# V2.net
KiCad netlist of a schematic drawn in EAGLE
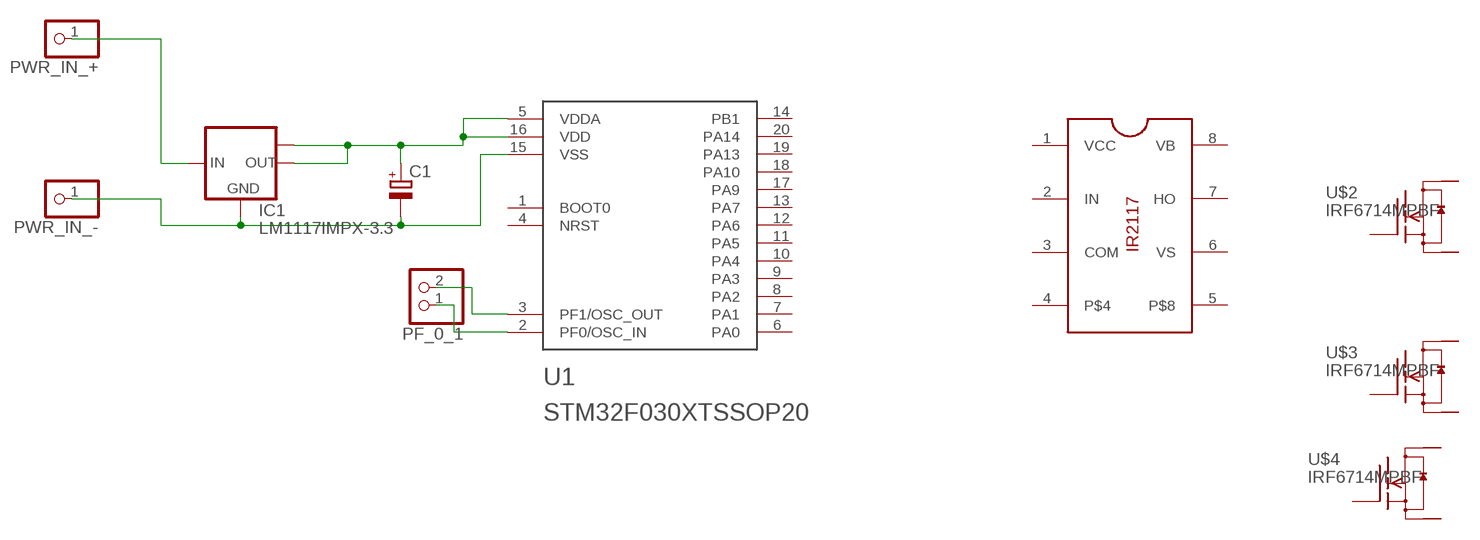
[diagram p0: schematic, sheet 1]

(export (version "E")
  (design (tool "Eeschema 10.0.6"))
  (components
    (comp (ref "C1")
      (value "CPOL-EUSMCD")
      (footprint "eagle-import:SMC_D")
      (libsource (lib "eagle-import") (part "CPOL-EUSMCD"))
    )
    (comp (ref "IC1")
      (value "LM1117IMPX-3.3")
      (footprint "eagle-import:SOT223")
      (libsource (lib "eagle-import") (part "LM1117IMPX-3.3"))
    )
    (comp (ref "PF_0_1")
      (value "PINHD-1X2")
      (footprint "eagle-import:1X02")
      (libsource (lib "eagle-import") (part "PINHD-1X2"))
    )
    (comp (ref "PWR_IN_+")
      (value "PINHD-1X1")
      (footprint "eagle-import:1X01")
      (libsource (lib "eagle-import") (part "PINHD-1X1"))
    )
    (comp (ref "PWR_IN_-")
      (value "PINHD-1X1")
      (footprint "eagle-import:1X01")
      (libsource (lib "eagle-import") (part "PINHD-1X1"))
    )
    (comp (ref "U$1")
      (value "IR2117SPBF")
      (footprint "eagle-import:SO8")
      (libsource (lib "eagle-import") (part "IR2117SPBF"))
    )
    (comp (ref "U$2")
      (value "IRF6714MPBF")
      (footprint "eagle-import:DIRECTFET-MX")
      (libsource (lib "eagle-import") (part "IRF6714MPBF"))
    )
    (comp (ref "U$3")
      (value "IRF6714MPBF")
      (footprint "eagle-import:DIRECTFET-MX")
      (libsource (lib "eagle-import") (part "IRF6714MPBF"))
    )
    (comp (ref "U$4")
      (value "IRF6714MPBF")
      (footprint "eagle-import:DIRECTFET-MX")
      (libsource (lib "eagle-import") (part "IRF6714MPBF"))
    )
    (comp (ref "U1")
      (value "STM32F030XTSSOP20")
      (footprint "eagle-import:TSSOP-20")
      (libsource (lib "eagle-import") (part "STM32F030XTSSOP20"))
    )
  )
  (nets
    (net (code "1") (name "Net-(IC1-GND)") (class "Default")
      (node (ref "C1") (pin "-") (pinfunction "-_-") (pintype "passive"))
      (node (ref "IC1") (pin "1") (pinfunction "GND_1") (pintype "input"))
      (node (ref "PWR_IN_-") (pin "1") (pinfunction "1_1") (pintype "passive"))
      (node (ref "U1") (pin "15") (pinfunction "VSS_15") (pintype "bidirectional"))
    )
    (net (code "2") (name "Net-(IC1-IN)") (class "Default")
      (node (ref "IC1") (pin "3") (pinfunction "IN_3") (pintype "input"))
      (node (ref "PWR_IN_+") (pin "1") (pinfunction "1_1") (pintype "passive"))
    )
    (net (code "3") (name "Net-(IC1-OUT)") (class "Default")
      (node (ref "C1") (pin "+") (pinfunction "+_+") (pintype "passive"))
      (node (ref "IC1") (pin "2") (pinfunction "OUT_2") (pintype "passive"))
      (node (ref "IC1") (pin "TAB") (pinfunction "OUT1_TAB") (pintype "passive"))
      (node (ref "U1") (pin "16") (pinfunction "VDD_16") (pintype "bidirectional"))
      (node (ref "U1") (pin "5") (pinfunction "VDDA_5") (pintype "bidirectional"))
    )
    (net (code "4") (name "Net-(U1-PF0{slash}OSC_IN)") (class "Default")
      (node (ref "PF_0_1") (pin "1") (pinfunction "1_1") (pintype "passive"))
      (node (ref "U1") (pin "2") (pinfunction "PF0/OSC_IN_2") (pintype "bidirectional"))
    )
    (net (code "5") (name "Net-(U1-PF1{slash}OSC_OUT)") (class "Default")
      (node (ref "PF_0_1") (pin "2") (pinfunction "2_2") (pintype "passive"))
      (node (ref "U1") (pin "3") (pinfunction "PF1/OSC_OUT_3") (pintype "bidirectional"))
    )
    (net (code "6") (name "unconnected-(U$1-COM-Pad3)") (class "Default")
      (node (ref "U$1") (pin "3") (pinfunction "COM_3") (pintype "bidirectional"))
    )
    (net (code "7") (name "unconnected-(U$1-HO-Pad7)") (class "Default")
      (node (ref "U$1") (pin "7") (pinfunction "HO_7") (pintype "bidirectional"))
    )
    (net (code "8") (name "unconnected-(U$1-IN-Pad2)") (class "Default")
      (node (ref "U$1") (pin "2") (pinfunction "IN_2") (pintype "bidirectional"))
    )
    (net (code "9") (name "unconnected-(U$1-P$4-Pad4)") (class "Default")
      (node (ref "U$1") (pin "4") (pinfunction "P$4_4") (pintype "bidirectional"))
    )
    (net (code "10") (name "unconnected-(U$1-P$8-Pad5)") (class "Default")
      (node (ref "U$1") (pin "5") (pinfunction "P$8_5") (pintype "bidirectional"))
    )
    (net (code "11") (name "unconnected-(U$1-VB-Pad8)") (class "Default")
      (node (ref "U$1") (pin "8") (pinfunction "VB_8") (pintype "bidirectional"))
    )
    (net (code "12") (name "unconnected-(U$1-VCC-Pad1)") (class "Default")
      (node (ref "U$1") (pin "1") (pinfunction "VCC_1") (pintype "bidirectional"))
    )
    (net (code "13") (name "unconnected-(U$1-VS-Pad6)") (class "Default")
      (node (ref "U$1") (pin "6") (pinfunction "VS_6") (pintype "bidirectional"))
    )
    (net (code "14") (name "unconnected-(U$2-D-PadD(V))") (class "Default")
      (node (ref "U$2") (pin "D(V)") (pinfunction "D_D(V)") (pintype "passive"))
    )
    (net (code "15") (name "unconnected-(U$2-PadG)") (class "Default")
      (node (ref "U$2") (pin "G") (pinfunction "G_G") (pintype "passive"))
    )
    (net (code "16") (name "unconnected-(U$2-PadS)") (class "Default")
      (node (ref "U$2") (pin "S") (pinfunction "S_S") (pintype "passive"))
    )
    (net (code "17") (name "unconnected-(U$3-D-PadD(V))") (class "Default")
      (node (ref "U$3") (pin "D(V)") (pinfunction "D_D(V)") (pintype "passive"))
    )
    (net (code "18") (name "unconnected-(U$3-PadG)") (class "Default")
      (node (ref "U$3") (pin "G") (pinfunction "G_G") (pintype "passive"))
    )
    (net (code "19") (name "unconnected-(U$3-PadS)") (class "Default")
      (node (ref "U$3") (pin "S") (pinfunction "S_S") (pintype "passive"))
    )
    (net (code "20") (name "unconnected-(U$4-D-PadD(V))") (class "Default")
      (node (ref "U$4") (pin "D(V)") (pinfunction "D_D(V)") (pintype "passive"))
    )
    (net (code "21") (name "unconnected-(U$4-PadG)") (class "Default")
      (node (ref "U$4") (pin "G") (pinfunction "G_G") (pintype "passive"))
    )
    (net (code "22") (name "unconnected-(U$4-PadS)") (class "Default")
      (node (ref "U$4") (pin "S") (pinfunction "S_S") (pintype "passive"))
    )
    (net (code "23") (name "unconnected-(U1-BOOT0-Pad1)") (class "Default")
      (node (ref "U1") (pin "1") (pinfunction "BOOT0_1") (pintype "bidirectional"))
    )
    (net (code "24") (name "unconnected-(U1-NRST-Pad4)") (class "Default")
      (node (ref "U1") (pin "4") (pinfunction "NRST_4") (pintype "bidirectional"))
    )
    (net (code "25") (name "unconnected-(U1-PA0-Pad6)") (class "Default")
      (node (ref "U1") (pin "6") (pinfunction "PA0_6") (pintype "bidirectional"))
    )
    (net (code "26") (name "unconnected-(U1-PA1-Pad7)") (class "Default")
      (node (ref "U1") (pin "7") (pinfunction "PA1_7") (pintype "bidirectional"))
    )
    (net (code "27") (name "unconnected-(U1-PA2-Pad8)") (class "Default")
      (node (ref "U1") (pin "8") (pinfunction "PA2_8") (pintype "bidirectional"))
    )
    (net (code "28") (name "unconnected-(U1-PA3-Pad9)") (class "Default")
      (node (ref "U1") (pin "9") (pinfunction "PA3_9") (pintype "bidirectional"))
    )
    (net (code "29") (name "unconnected-(U1-PA4-Pad10)") (class "Default")
      (node (ref "U1") (pin "10") (pinfunction "PA4_10") (pintype "bidirectional"))
    )
    (net (code "30") (name "unconnected-(U1-PA5-Pad11)") (class "Default")
      (node (ref "U1") (pin "11") (pinfunction "PA5_11") (pintype "bidirectional"))
    )
    (net (code "31") (name "unconnected-(U1-PA6-Pad12)") (class "Default")
      (node (ref "U1") (pin "12") (pinfunction "PA6_12") (pintype "bidirectional"))
    )
    (net (code "32") (name "unconnected-(U1-PA7-Pad13)") (class "Default")
      (node (ref "U1") (pin "13") (pinfunction "PA7_13") (pintype "bidirectional"))
    )
    (net (code "33") (name "unconnected-(U1-PA9-Pad17)") (class "Default")
      (node (ref "U1") (pin "17") (pinfunction "PA9_17") (pintype "bidirectional"))
    )
    (net (code "34") (name "unconnected-(U1-PA10-Pad18)") (class "Default")
      (node (ref "U1") (pin "18") (pinfunction "PA10_18") (pintype "bidirectional"))
    )
    (net (code "35") (name "unconnected-(U1-PA13-Pad19)") (class "Default")
      (node (ref "U1") (pin "19") (pinfunction "PA13_19") (pintype "bidirectional"))
    )
    (net (code "36") (name "unconnected-(U1-PA14-Pad20)") (class "Default")
      (node (ref "U1") (pin "20") (pinfunction "PA14_20") (pintype "bidirectional"))
    )
    (net (code "37") (name "unconnected-(U1-PB1-Pad14)") (class "Default")
      (node (ref "U1") (pin "14") (pinfunction "PB1_14") (pintype "bidirectional"))
    )
  )
)
